# photocell_mk3.net
KiCad netlist of a schematic drawn in EAGLE
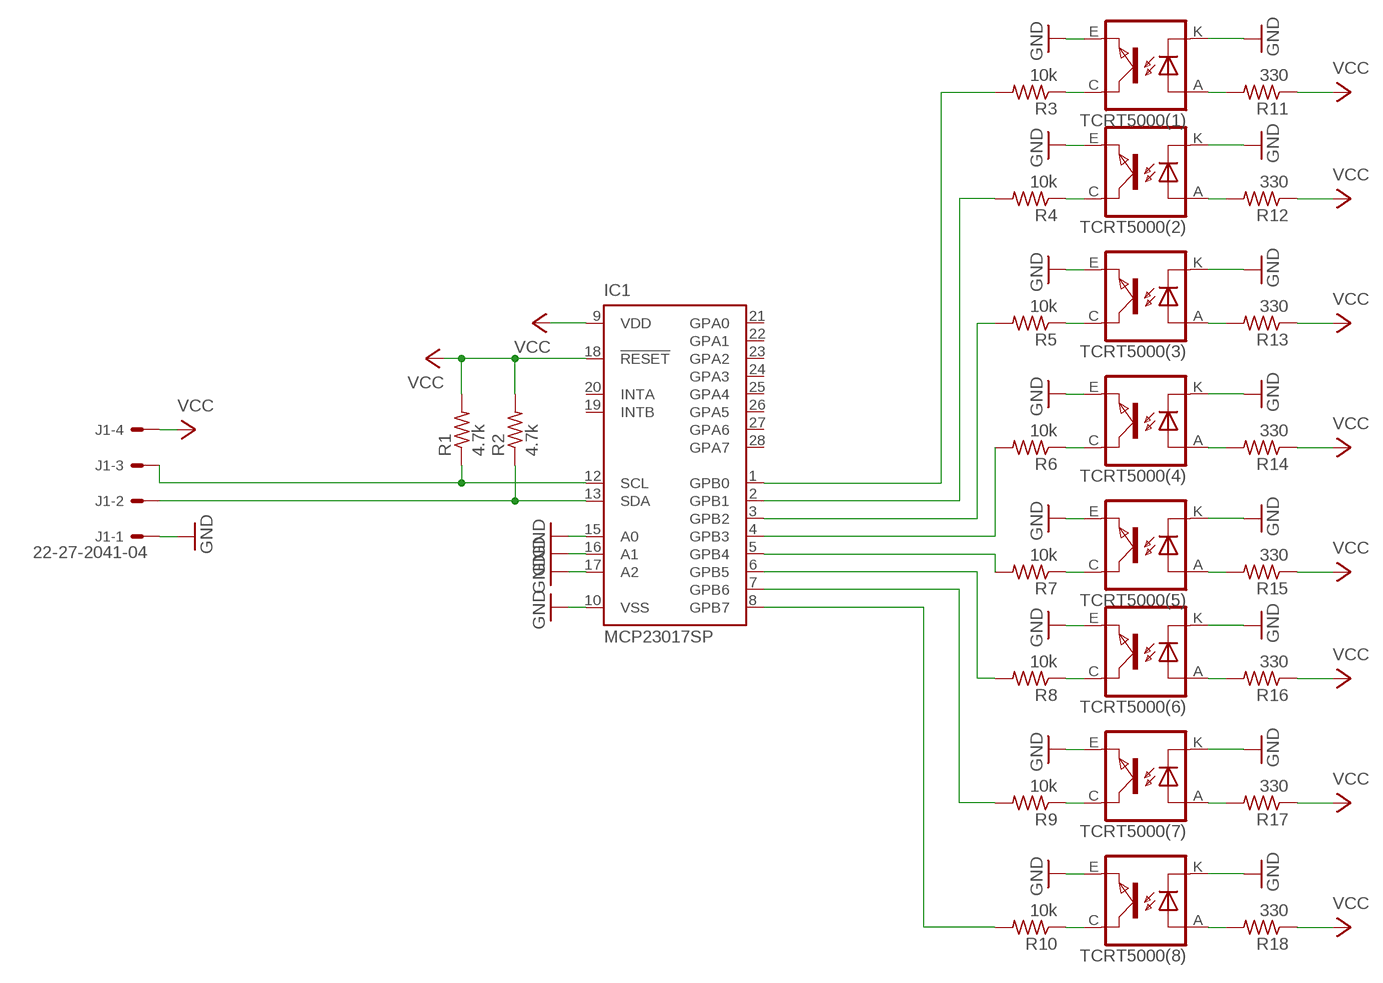
[diagram p0: schematic, sheet 1]

(export (version "E")
  (design (tool "Eeschema 10.0.6"))
  (components
    (comp (ref "IC1")
      (value "MCP23017SP")
      (footprint "eagle-import:DIL28-3")
      (fields (field (name "MF") "MICROCHIP") (field (name "MPN") "MCP23017-E/SP"))
      (libsource (lib "eagle-import") (part "MCP23017SP"))
    )
    (comp (ref "J1")
      (value "22-27-2041-04")
      (footprint "eagle-import:6410-04")
      (libsource (lib "eagle-import") (part "22-?-0427-2041"))
    )
    (comp (ref "R1")
      (value "4.7k")
      (footprint "eagle-import:0204_7")
      (libsource (lib "eagle-import") (part "R-US_0204/7"))
    )
    (comp (ref "R2")
      (value "4.7k")
      (footprint "eagle-import:0204_7")
      (libsource (lib "eagle-import") (part "R-US_0204/7"))
    )
    (comp (ref "R3")
      (value "10k")
      (footprint "eagle-import:0204_7")
      (libsource (lib "eagle-import") (part "R-US_0204/7"))
    )
    (comp (ref "R4")
      (value "10k")
      (footprint "eagle-import:0204_7")
      (libsource (lib "eagle-import") (part "R-US_0204/7"))
    )
    (comp (ref "R5")
      (value "10k")
      (footprint "eagle-import:0204_7")
      (libsource (lib "eagle-import") (part "R-US_0204/7"))
    )
    (comp (ref "R6")
      (value "10k")
      (footprint "eagle-import:0204_7")
      (libsource (lib "eagle-import") (part "R-US_0204/7"))
    )
    (comp (ref "R7")
      (value "10k")
      (footprint "eagle-import:0204_7")
      (libsource (lib "eagle-import") (part "R-US_0204/7"))
    )
    (comp (ref "R8")
      (value "10k")
      (footprint "eagle-import:0204_7")
      (libsource (lib "eagle-import") (part "R-US_0204/7"))
    )
    (comp (ref "R9")
      (value "10k")
      (footprint "eagle-import:0204_7")
      (libsource (lib "eagle-import") (part "R-US_0204/7"))
    )
    (comp (ref "R10")
      (value "10k")
      (footprint "eagle-import:0204_7")
      (libsource (lib "eagle-import") (part "R-US_0204/7"))
    )
    (comp (ref "R11")
      (value "330")
      (footprint "eagle-import:0204_7")
      (libsource (lib "eagle-import") (part "R-US_0204/7"))
    )
    (comp (ref "R12")
      (value "330")
      (footprint "eagle-import:0204_7")
      (libsource (lib "eagle-import") (part "R-US_0204/7"))
    )
    (comp (ref "R13")
      (value "330")
      (footprint "eagle-import:0204_7")
      (libsource (lib "eagle-import") (part "R-US_0204/7"))
    )
    (comp (ref "R14")
      (value "330")
      (footprint "eagle-import:0204_7")
      (libsource (lib "eagle-import") (part "R-US_0204/7"))
    )
    (comp (ref "R15")
      (value "330")
      (footprint "eagle-import:0204_7")
      (libsource (lib "eagle-import") (part "R-US_0204/7"))
    )
    (comp (ref "R16")
      (value "330")
      (footprint "eagle-import:0204_7")
      (libsource (lib "eagle-import") (part "R-US_0204/7"))
    )
    (comp (ref "R17")
      (value "330")
      (footprint "eagle-import:0204_7")
      (libsource (lib "eagle-import") (part "R-US_0204/7"))
    )
    (comp (ref "R18")
      (value "330")
      (footprint "eagle-import:0204_7")
      (libsource (lib "eagle-import") (part "R-US_0204/7"))
    )
    (comp (ref "TCRT5000(1)")
      (value "TCRT5000")
      (footprint "eagle-import:TCRT5000")
      (libsource (lib "eagle-import") (part "TCRT5000"))
    )
    (comp (ref "TCRT5000(2)")
      (value "TCRT5000")
      (footprint "eagle-import:TCRT5000")
      (libsource (lib "eagle-import") (part "TCRT5000"))
    )
    (comp (ref "TCRT5000(3)")
      (value "TCRT5000")
      (footprint "eagle-import:TCRT5000")
      (libsource (lib "eagle-import") (part "TCRT5000"))
    )
    (comp (ref "TCRT5000(4)")
      (value "TCRT5000")
      (footprint "eagle-import:TCRT5000")
      (libsource (lib "eagle-import") (part "TCRT5000"))
    )
    (comp (ref "TCRT5000(5)")
      (value "TCRT5000")
      (footprint "eagle-import:TCRT5000")
      (libsource (lib "eagle-import") (part "TCRT5000"))
    )
    (comp (ref "TCRT5000(6)")
      (value "TCRT5000")
      (footprint "eagle-import:TCRT5000")
      (libsource (lib "eagle-import") (part "TCRT5000"))
    )
    (comp (ref "TCRT5000(7)")
      (value "TCRT5000")
      (footprint "eagle-import:TCRT5000")
      (libsource (lib "eagle-import") (part "TCRT5000"))
    )
    (comp (ref "TCRT5000(8)")
      (value "TCRT5000")
      (footprint "eagle-import:TCRT5000")
      (libsource (lib "eagle-import") (part "TCRT5000"))
    )
  )
  (nets
    (net (code "1") (name "GND") (class "Default")
      (node (ref "IC1") (pin "10") (pinfunction "VSS_10") (pintype "power_in"))
      (node (ref "IC1") (pin "15") (pinfunction "A0_15") (pintype "input"))
      (node (ref "IC1") (pin "16") (pinfunction "A1_16") (pintype "input"))
      (node (ref "IC1") (pin "17") (pinfunction "A2_17") (pintype "input"))
      (node (ref "J1") (pin "1") (pinfunction "S_1") (pintype "passive"))
      (node (ref "TCRT5000(1)") (pin "E") (pinfunction "EMITTER_E") (pintype "passive"))
      (node (ref "TCRT5000(1)") (pin "K") (pinfunction "CATHODE_K") (pintype "passive"))
      (node (ref "TCRT5000(2)") (pin "E") (pinfunction "EMITTER_E") (pintype "passive"))
      (node (ref "TCRT5000(2)") (pin "K") (pinfunction "CATHODE_K") (pintype "passive"))
      (node (ref "TCRT5000(3)") (pin "E") (pinfunction "EMITTER_E") (pintype "passive"))
      (node (ref "TCRT5000(3)") (pin "K") (pinfunction "CATHODE_K") (pintype "passive"))
      (node (ref "TCRT5000(4)") (pin "E") (pinfunction "EMITTER_E") (pintype "passive"))
      (node (ref "TCRT5000(4)") (pin "K") (pinfunction "CATHODE_K") (pintype "passive"))
      (node (ref "TCRT5000(5)") (pin "E") (pinfunction "EMITTER_E") (pintype "passive"))
      (node (ref "TCRT5000(5)") (pin "K") (pinfunction "CATHODE_K") (pintype "passive"))
      (node (ref "TCRT5000(6)") (pin "E") (pinfunction "EMITTER_E") (pintype "passive"))
      (node (ref "TCRT5000(6)") (pin "K") (pinfunction "CATHODE_K") (pintype "passive"))
      (node (ref "TCRT5000(7)") (pin "E") (pinfunction "EMITTER_E") (pintype "passive"))
      (node (ref "TCRT5000(7)") (pin "K") (pinfunction "CATHODE_K") (pintype "passive"))
      (node (ref "TCRT5000(8)") (pin "E") (pinfunction "EMITTER_E") (pintype "passive"))
      (node (ref "TCRT5000(8)") (pin "K") (pinfunction "CATHODE_K") (pintype "passive"))
    )
    (net (code "2") (name "Net-(IC1-GPB0)") (class "Default")
      (node (ref "IC1") (pin "1") (pinfunction "GPB0_1") (pintype "bidirectional"))
      (node (ref "R3") (pin "2") (pinfunction "2_2") (pintype "passive"))
    )
    (net (code "3") (name "Net-(IC1-GPB1)") (class "Default")
      (node (ref "IC1") (pin "2") (pinfunction "GPB1_2") (pintype "bidirectional"))
      (node (ref "R4") (pin "2") (pinfunction "2_2") (pintype "passive"))
    )
    (net (code "4") (name "Net-(IC1-GPB2)") (class "Default")
      (node (ref "IC1") (pin "3") (pinfunction "GPB2_3") (pintype "bidirectional"))
      (node (ref "R5") (pin "2") (pinfunction "2_2") (pintype "passive"))
    )
    (net (code "5") (name "Net-(IC1-GPB3)") (class "Default")
      (node (ref "IC1") (pin "4") (pinfunction "GPB3_4") (pintype "bidirectional"))
      (node (ref "R6") (pin "2") (pinfunction "2_2") (pintype "passive"))
    )
    (net (code "6") (name "Net-(IC1-GPB4)") (class "Default")
      (node (ref "IC1") (pin "5") (pinfunction "GPB4_5") (pintype "bidirectional"))
      (node (ref "R7") (pin "2") (pinfunction "2_2") (pintype "passive"))
    )
    (net (code "7") (name "Net-(IC1-GPB5)") (class "Default")
      (node (ref "IC1") (pin "6") (pinfunction "GPB5_6") (pintype "bidirectional"))
      (node (ref "R8") (pin "2") (pinfunction "2_2") (pintype "passive"))
    )
    (net (code "8") (name "Net-(IC1-GPB6)") (class "Default")
      (node (ref "IC1") (pin "7") (pinfunction "GPB6_7") (pintype "bidirectional"))
      (node (ref "R9") (pin "2") (pinfunction "2_2") (pintype "passive"))
    )
    (net (code "9") (name "Net-(IC1-GPB7)") (class "Default")
      (node (ref "IC1") (pin "8") (pinfunction "GPB7_8") (pintype "bidirectional"))
      (node (ref "R10") (pin "2") (pinfunction "2_2") (pintype "passive"))
    )
    (net (code "10") (name "Net-(IC1-SCL)") (class "Default")
      (node (ref "IC1") (pin "12") (pinfunction "SCL_12") (pintype "input"))
      (node (ref "J1") (pin "3") (pinfunction "S_3") (pintype "passive"))
      (node (ref "R1") (pin "1") (pinfunction "1_1") (pintype "passive"))
    )
    (net (code "11") (name "Net-(IC1-SDA)") (class "Default")
      (node (ref "IC1") (pin "13") (pinfunction "SDA_13") (pintype "bidirectional"))
      (node (ref "J1") (pin "2") (pinfunction "S_2") (pintype "passive"))
      (node (ref "R2") (pin "1") (pinfunction "1_1") (pintype "passive"))
    )
    (net (code "12") (name "Net-(TCRT5000(1)-ANODE)") (class "Default")
      (node (ref "R11") (pin "2") (pinfunction "2_2") (pintype "passive"))
      (node (ref "TCRT5000(1)") (pin "A") (pinfunction "ANODE_A") (pintype "passive"))
    )
    (net (code "13") (name "Net-(TCRT5000(1)-COLLECTOR)") (class "Default")
      (node (ref "R3") (pin "1") (pinfunction "1_1") (pintype "passive"))
      (node (ref "TCRT5000(1)") (pin "C") (pinfunction "COLLECTOR_C") (pintype "passive"))
    )
    (net (code "14") (name "Net-(TCRT5000(2)-ANODE)") (class "Default")
      (node (ref "R12") (pin "2") (pinfunction "2_2") (pintype "passive"))
      (node (ref "TCRT5000(2)") (pin "A") (pinfunction "ANODE_A") (pintype "passive"))
    )
    (net (code "15") (name "Net-(TCRT5000(2)-COLLECTOR)") (class "Default")
      (node (ref "R4") (pin "1") (pinfunction "1_1") (pintype "passive"))
      (node (ref "TCRT5000(2)") (pin "C") (pinfunction "COLLECTOR_C") (pintype "passive"))
    )
    (net (code "16") (name "Net-(TCRT5000(3)-ANODE)") (class "Default")
      (node (ref "R13") (pin "2") (pinfunction "2_2") (pintype "passive"))
      (node (ref "TCRT5000(3)") (pin "A") (pinfunction "ANODE_A") (pintype "passive"))
    )
    (net (code "17") (name "Net-(TCRT5000(3)-COLLECTOR)") (class "Default")
      (node (ref "R5") (pin "1") (pinfunction "1_1") (pintype "passive"))
      (node (ref "TCRT5000(3)") (pin "C") (pinfunction "COLLECTOR_C") (pintype "passive"))
    )
    (net (code "18") (name "Net-(TCRT5000(4)-ANODE)") (class "Default")
      (node (ref "R14") (pin "2") (pinfunction "2_2") (pintype "passive"))
      (node (ref "TCRT5000(4)") (pin "A") (pinfunction "ANODE_A") (pintype "passive"))
    )
    (net (code "19") (name "Net-(TCRT5000(4)-COLLECTOR)") (class "Default")
      (node (ref "R6") (pin "1") (pinfunction "1_1") (pintype "passive"))
      (node (ref "TCRT5000(4)") (pin "C") (pinfunction "COLLECTOR_C") (pintype "passive"))
    )
    (net (code "20") (name "Net-(TCRT5000(5)-ANODE)") (class "Default")
      (node (ref "R15") (pin "2") (pinfunction "2_2") (pintype "passive"))
      (node (ref "TCRT5000(5)") (pin "A") (pinfunction "ANODE_A") (pintype "passive"))
    )
    (net (code "21") (name "Net-(TCRT5000(5)-COLLECTOR)") (class "Default")
      (node (ref "R7") (pin "1") (pinfunction "1_1") (pintype "passive"))
      (node (ref "TCRT5000(5)") (pin "C") (pinfunction "COLLECTOR_C") (pintype "passive"))
    )
    (net (code "22") (name "Net-(TCRT5000(6)-ANODE)") (class "Default")
      (node (ref "R16") (pin "2") (pinfunction "2_2") (pintype "passive"))
      (node (ref "TCRT5000(6)") (pin "A") (pinfunction "ANODE_A") (pintype "passive"))
    )
    (net (code "23") (name "Net-(TCRT5000(6)-COLLECTOR)") (class "Default")
      (node (ref "R8") (pin "1") (pinfunction "1_1") (pintype "passive"))
      (node (ref "TCRT5000(6)") (pin "C") (pinfunction "COLLECTOR_C") (pintype "passive"))
    )
    (net (code "24") (name "Net-(TCRT5000(7)-ANODE)") (class "Default")
      (node (ref "R17") (pin "2") (pinfunction "2_2") (pintype "passive"))
      (node (ref "TCRT5000(7)") (pin "A") (pinfunction "ANODE_A") (pintype "passive"))
    )
    (net (code "25") (name "Net-(TCRT5000(7)-COLLECTOR)") (class "Default")
      (node (ref "R9") (pin "1") (pinfunction "1_1") (pintype "passive"))
      (node (ref "TCRT5000(7)") (pin "C") (pinfunction "COLLECTOR_C") (pintype "passive"))
    )
    (net (code "26") (name "Net-(TCRT5000(8)-ANODE)") (class "Default")
      (node (ref "R18") (pin "2") (pinfunction "2_2") (pintype "passive"))
      (node (ref "TCRT5000(8)") (pin "A") (pinfunction "ANODE_A") (pintype "passive"))
    )
    (net (code "27") (name "Net-(TCRT5000(8)-COLLECTOR)") (class "Default")
      (node (ref "R10") (pin "1") (pinfunction "1_1") (pintype "passive"))
      (node (ref "TCRT5000(8)") (pin "C") (pinfunction "COLLECTOR_C") (pintype "passive"))
    )
    (net (code "28") (name "VCC") (class "Default")
      (node (ref "IC1") (pin "18") (pinfunction "~{RESET}_18") (pintype "input"))
      (node (ref "IC1") (pin "9") (pinfunction "VDD_9") (pintype "power_in"))
      (node (ref "J1") (pin "4") (pinfunction "S_4") (pintype "passive"))
      (node (ref "R1") (pin "2") (pinfunction "2_2") (pintype "passive"))
      (node (ref "R11") (pin "1") (pinfunction "1_1") (pintype "passive"))
      (node (ref "R12") (pin "1") (pinfunction "1_1") (pintype "passive"))
      (node (ref "R13") (pin "1") (pinfunction "1_1") (pintype "passive"))
      (node (ref "R14") (pin "1") (pinfunction "1_1") (pintype "passive"))
      (node (ref "R15") (pin "1") (pinfunction "1_1") (pintype "passive"))
      (node (ref "R16") (pin "1") (pinfunction "1_1") (pintype "passive"))
      (node (ref "R17") (pin "1") (pinfunction "1_1") (pintype "passive"))
      (node (ref "R18") (pin "1") (pinfunction "1_1") (pintype "passive"))
      (node (ref "R2") (pin "2") (pinfunction "2_2") (pintype "passive"))
    )
    (net (code "29") (name "unconnected-(IC1-GPA0-Pad21)") (class "Default")
      (node (ref "IC1") (pin "21") (pinfunction "GPA0_21") (pintype "bidirectional"))
    )
    (net (code "30") (name "unconnected-(IC1-GPA1-Pad22)") (class "Default")
      (node (ref "IC1") (pin "22") (pinfunction "GPA1_22") (pintype "bidirectional"))
    )
    (net (code "31") (name "unconnected-(IC1-GPA2-Pad23)") (class "Default")
      (node (ref "IC1") (pin "23") (pinfunction "GPA2_23") (pintype "bidirectional"))
    )
    (net (code "32") (name "unconnected-(IC1-GPA3-Pad24)") (class "Default")
      (node (ref "IC1") (pin "24") (pinfunction "GPA3_24") (pintype "bidirectional"))
    )
    (net (code "33") (name "unconnected-(IC1-GPA4-Pad25)") (class "Default")
      (node (ref "IC1") (pin "25") (pinfunction "GPA4_25") (pintype "bidirectional"))
    )
    (net (code "34") (name "unconnected-(IC1-GPA5-Pad26)") (class "Default")
      (node (ref "IC1") (pin "26") (pinfunction "GPA5_26") (pintype "bidirectional"))
    )
    (net (code "35") (name "unconnected-(IC1-GPA6-Pad27)") (class "Default")
      (node (ref "IC1") (pin "27") (pinfunction "GPA6_27") (pintype "bidirectional"))
    )
    (net (code "36") (name "unconnected-(IC1-GPA7-Pad28)") (class "Default")
      (node (ref "IC1") (pin "28") (pinfunction "GPA7_28") (pintype "bidirectional"))
    )
    (net (code "37") (name "unconnected-(IC1-INTA-Pad20)") (class "Default")
      (node (ref "IC1") (pin "20") (pinfunction "INTA_20") (pintype "output"))
    )
    (net (code "38") (name "unconnected-(IC1-INTB-Pad19)") (class "Default")
      (node (ref "IC1") (pin "19") (pinfunction "INTB_19") (pintype "output"))
    )
  )
)
